# Acoustics_Connections_RP2040.net
KiCad netlist of a schematic drawn in Altium Designer
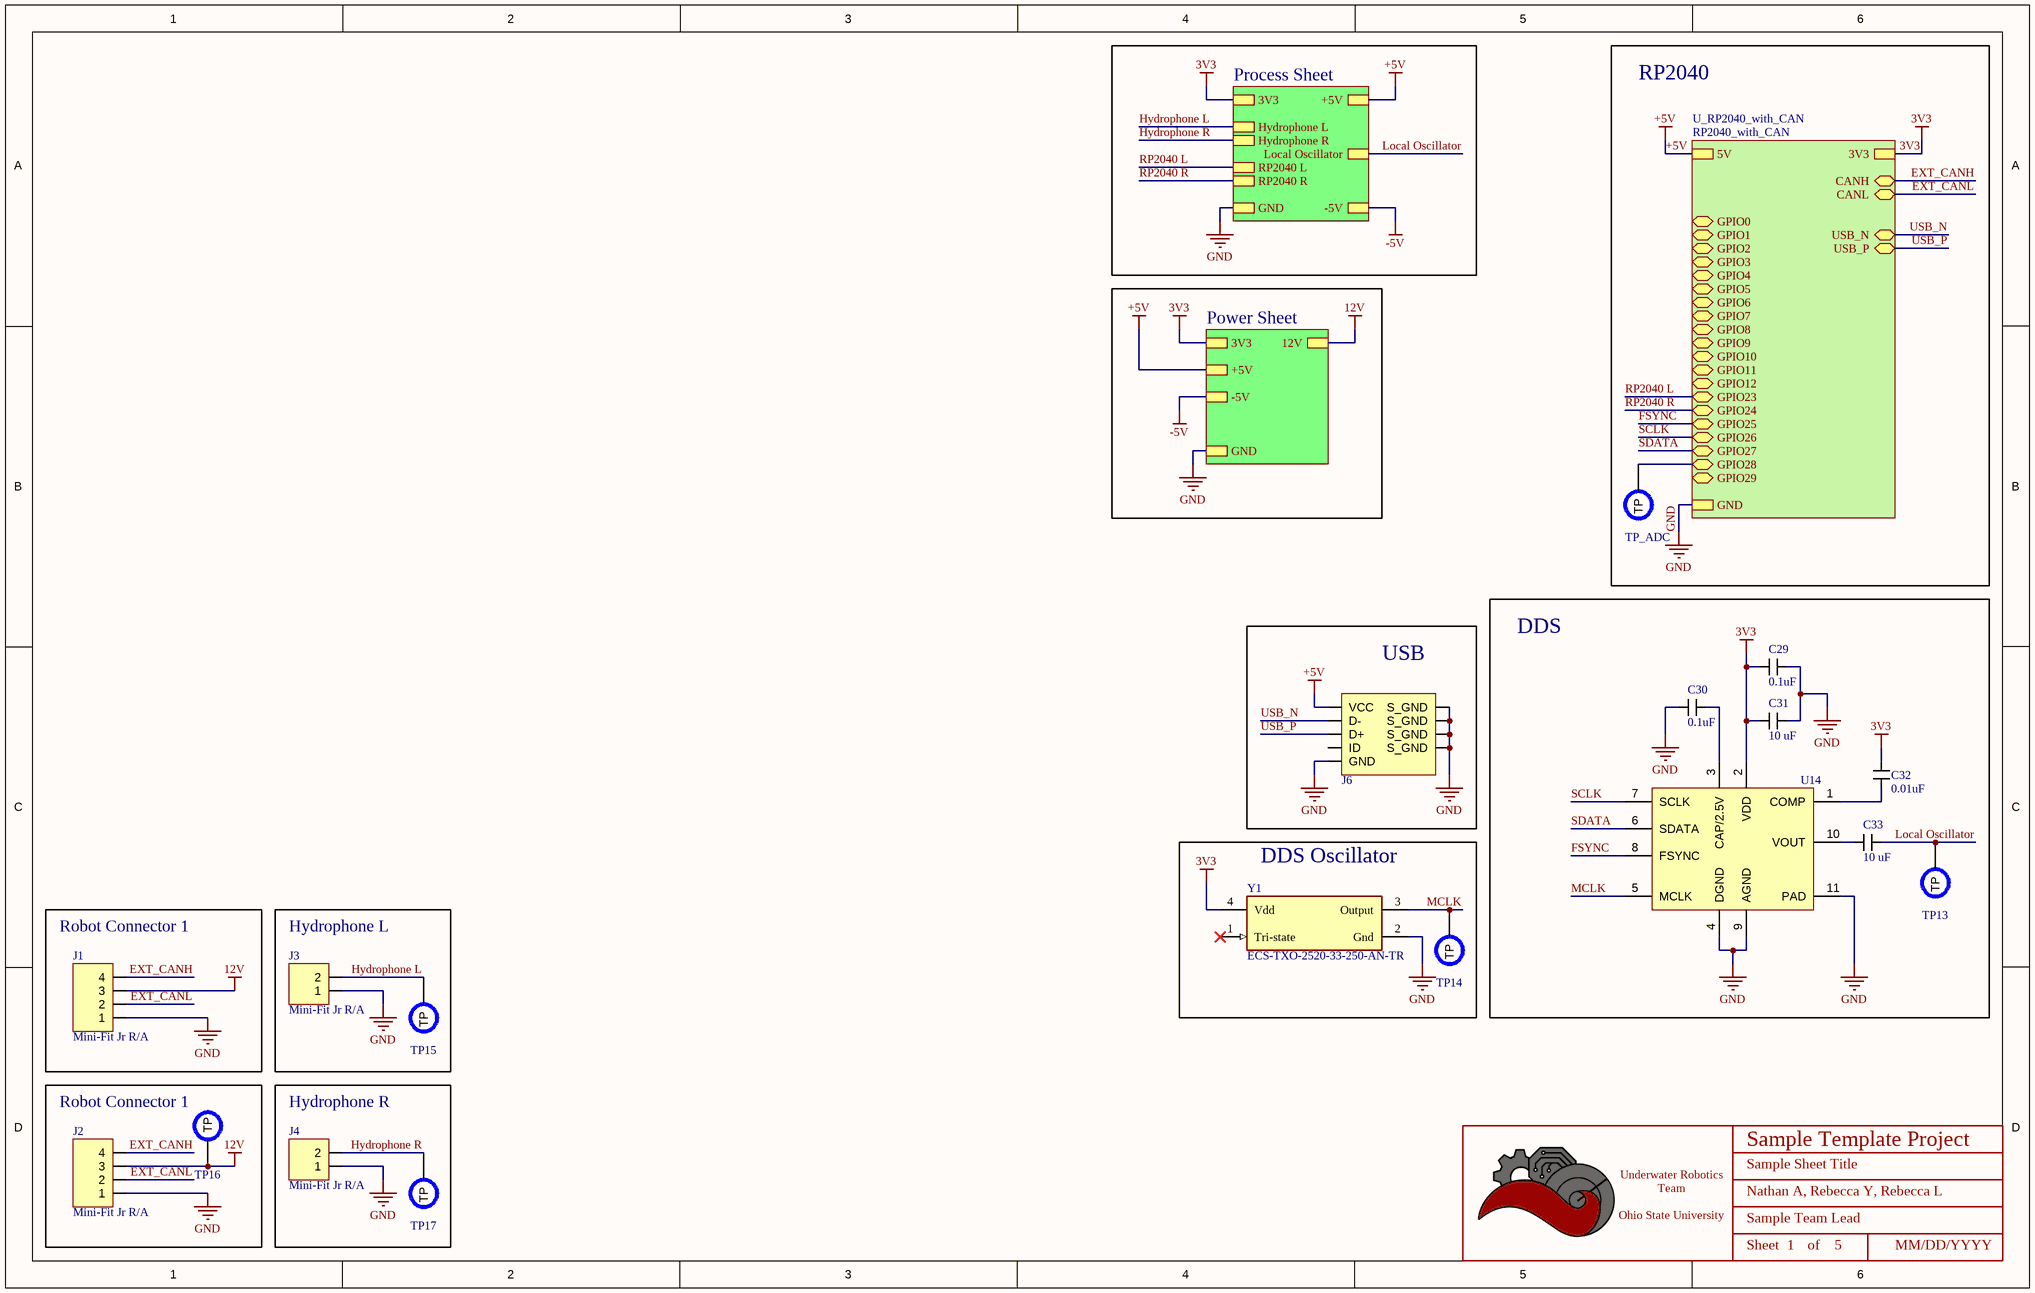
[diagram p0: [Acoustics] Connections & RP2040.SchDoc]

(export (version "E")
  (design (tool "Eeschema 10.0.6"))
  (components
    (comp (ref "C29")
      (value "0.1uF")
      (footprint "CAPACITOR_0603")
      (description "Cap 100nF 6.3V +/-10%\r\nCeramic 0603")
      (fields
        (field (name "TOLERANCE") "+/- 10%")
        (field (name "VOLTAGE") "6.3V")
        (field (name "MADE BY") "Flip B")
      )
      (libsource (lib "Capacitors") (part "CAPACITOR_0.1uF_0603"))
    )
    (comp (ref "C30")
      (value "0.1uF")
      (footprint "CAPACITOR_0603")
      (description "Cap 100nF 6.3V +/-10%\r\nCeramic 0603")
      (fields
        (field (name "TOLERANCE") "+/- 10%")
        (field (name "VOLTAGE") "6.3V")
        (field (name "MADE BY") "Flip B")
      )
      (libsource (lib "Capacitors") (part "CAPACITOR_0.1uF_0603"))
    )
    (comp (ref "C31")
      (value "10uF Ceramic 6.3V")
      (footprint "CAPACITOR_0603")
      (description "Cap 10uF 6.3V +/-20%\r\nCeramic 0603")
      (fields
        (field (name "TOLERANCE") "+/- 20%")
        (field (name "VOLTAGE") "6.3V")
        (field (name "VALUE (UF)") "10 uF")
        (field (name "MADE BY") "Flip B")
      )
      (libsource (lib "Capacitors") (part "CAPACITOR_10uF_0603"))
    )
    (comp (ref "C32")
      (value "0.01uF")
      (footprint "CAPACITOR_0603")
      (description "10000 pF ±10% 50V Ceramic Capacitor X7R 0603 (1608 Metric)")
      (fields
        (field (name "TOLERANCE") "+/- 10%")
        (field (name "VOLTAGE") "6.3V")
        (field (name "MADE BY") "Flip B")
      )
      (libsource (lib "Capacitors") (part "CAPACITOR_0.01uF_0603_50V"))
    )
    (comp (ref "C33")
      (value "10uF Ceramic 6.3V")
      (footprint "CAPACITOR_0603")
      (description "Cap 10uF 6.3V +/-20%\r\nCeramic 0603")
      (fields
        (field (name "TOLERANCE") "+/- 20%")
        (field (name "VOLTAGE") "6.3V")
        (field (name "VALUE (UF)") "10 uF")
        (field (name "MADE BY") "Flip B")
      )
      (libsource (lib "Capacitors") (part "CAPACITOR_10uF_0603"))
    )
    (comp (ref "J1")
      (value "Mini-Fit Jr R/A")
      (footprint "CONN_MOLEX_MINIFIT JR_4 POS_R/A")
      (description "Molex Minifit Jr. 5569 \r\n4 Pos R/A Natural")
      (fields (field (name "MANUFACTURER") "Molex") (field (name "CREATED BY") "Flip B"))
      (libsource (lib "Connectors") (part "CONN_MOLEX_MINIFIT JR_4POS_R/A"))
    )
    (comp (ref "J2")
      (value "Mini-Fit Jr R/A")
      (footprint "CONN_MOLEX_MINIFIT JR_4 POS_R/A")
      (description "Molex Minifit Jr. 5569 \r\n4 Pos R/A Natural")
      (fields (field (name "MANUFACTURER") "Molex") (field (name "CREATED BY") "Flip B"))
      (libsource (lib "Connectors") (part "CONN_MOLEX_MINIFIT JR_4POS_R/A"))
    )
    (comp (ref "J3")
      (value "Mini-Fit Jr R/A")
      (footprint "CONN_MOLEX_MINIFIT JR_2 POS_R/A")
      (description "Molex Minifit Jr. 5569 \r\n2 Pos R/A Natural")
      (fields (field (name "MANUFACTURER") "Molex") (field (name "CREATED BY") "Robert P"))
      (libsource (lib "Connectors") (part "CONN_MOLEX_MINIFIT JR_2POS_R/A"))
    )
    (comp (ref "J4")
      (value "Mini-Fit Jr R/A")
      (footprint "CONN_MOLEX_MINIFIT JR_2 POS_R/A")
      (description "Molex Minifit Jr. 5569 \r\n2 Pos R/A Natural")
      (fields (field (name "MANUFACTURER") "Molex") (field (name "CREATED BY") "Robert P"))
      (libsource (lib "Connectors") (part "CONN_MOLEX_MINIFIT JR_2POS_R/A"))
    )
    (comp (ref "J6")
      (value "USB_MICRO R/A")
      (footprint "CONN_MINIUSB")
      (description "Amphenol Micro USB-B\r\nUSB2.0 5 Pin Right Angle SMD")
      (fields (field (name "MANUFACTURER") "Amphenol") (field (name "CREATED BY") "Flip B"))
      (libsource (lib "Connectors") (part "CONN_MICROUSB"))
    )
    (comp (ref "TP13")
      (value "PCB Test Point")
      (footprint "TESTPOINT_1.2MM")
      (fields (field (name "MADE BY") "Robert Pafford"))
      (libsource (lib "Connectors") (part "TESTPOINT"))
    )
    (comp (ref "TP14")
      (value "PCB Test Point")
      (footprint "TESTPOINT_1.2MM")
      (fields (field (name "MADE BY") "Robert Pafford"))
      (libsource (lib "Connectors") (part "TESTPOINT"))
    )
    (comp (ref "TP15")
      (value "PCB Test Point")
      (footprint "TESTPOINT_1.2MM")
      (fields (field (name "MADE BY") "Robert Pafford"))
      (libsource (lib "Connectors") (part "TESTPOINT"))
    )
    (comp (ref "TP16")
      (value "PCB Test Point")
      (footprint "TESTPOINT_1.2MM")
      (fields (field (name "MADE BY") "Robert Pafford"))
      (libsource (lib "Connectors") (part "TESTPOINT"))
    )
    (comp (ref "TP17")
      (value "PCB Test Point")
      (footprint "TESTPOINT_1.2MM")
      (fields (field (name "MADE BY") "Robert Pafford"))
      (libsource (lib "Connectors") (part "TESTPOINT"))
    )
    (comp (ref "TP_ADC")
      (value "PCB Test Point")
      (footprint "TESTPOINT_1.2MM")
      (fields (field (name "MADE BY") "Robert Pafford"))
      (libsource (lib "Connectors") (part "TESTPOINT"))
    )
    (comp (ref "U14")
      (value "IC DDS 5MHZ 10BIT 10LFCSP")
      (footprint "CP-10-9")
      (description "Direct Digital Synthesis IC 10 b 5 MHz 28 b Tuning 10-LFCSP-WD (3x3)")
      (libsource (lib "Integrated Circuits") (part "AD9837ACPZ"))
    )
    (comp (ref "Y1")
      (value "ECS-TXO-2520-33-250-AN-TR")
      (footprint "FP-ECS-TXO-2520-MFG")
      (description "XTAL OSC TCXO 25.0000MHZ HCMOS")
      (libsource (lib "Altium Content Vault") (part "04cd953f3cf158082f8c09fbdb924ef"))
    )
  )
  (nets
    (net (code "1") (name "+5V") (class "Default")
      (node (ref "J6") (pin "1") (pinfunction "VCC_1") (pintype "passive"))
    )
    (net (code "3") (name "/EXT_CANH") (class "Default")
      (node (ref "J1") (pin "4") (pinfunction "4_4") (pintype "passive"))
      (node (ref "J2") (pin "4") (pinfunction "4_4") (pintype "passive"))
    )
    (net (code "4") (name "/EXT_CANL") (class "Default")
      (node (ref "J1") (pin "2") (pinfunction "2_2") (pintype "passive"))
      (node (ref "J2") (pin "2") (pinfunction "2_2") (pintype "passive"))
    )
    (net (code "5") (name "/FSYNC") (class "Default")
      (node (ref "U14") (pin "8") (pinfunction "FSYNC_8") (pintype "passive"))
    )
    (net (code "19") (name "/GPIO28") (class "Default")
      (node (ref "TP_ADC") (pin "TP") (pinfunction "TP_TP") (pintype "passive"))
    )
    (net (code "21") (name "/Hydrophone L") (class "Default")
      (node (ref "J3") (pin "2") (pinfunction "2_2") (pintype "passive"))
      (node (ref "TP15") (pin "TP") (pinfunction "TP_TP") (pintype "passive"))
    )
    (net (code "22") (name "/Hydrophone R") (class "Default")
      (node (ref "J4") (pin "2") (pinfunction "2_2") (pintype "passive"))
      (node (ref "TP17") (pin "TP") (pinfunction "TP_TP") (pintype "passive"))
    )
    (net (code "23") (name "/Local Oscillator") (class "Default")
      (node (ref "C33") (pin "2") (pinfunction "2_2") (pintype "passive"))
      (node (ref "TP13") (pin "TP") (pinfunction "TP_TP") (pintype "passive"))
    )
    (net (code "24") (name "/MCLK") (class "Default")
      (node (ref "TP14") (pin "TP") (pinfunction "TP_TP") (pintype "passive"))
      (node (ref "U14") (pin "5") (pinfunction "MCLK_5") (pintype "passive"))
      (node (ref "Y1") (pin "3") (pinfunction "Output_3") (pintype "tri_state"))
    )
    (net (code "27") (name "/SCLK") (class "Default")
      (node (ref "U14") (pin "7") (pinfunction "SCLK_7") (pintype "passive"))
    )
    (net (code "28") (name "/SDATA") (class "Default")
      (node (ref "U14") (pin "6") (pinfunction "SDATA_6") (pintype "passive"))
    )
    (net (code "29") (name "/USB_N") (class "Default")
      (node (ref "J6") (pin "2") (pinfunction "D-_2") (pintype "passive"))
    )
    (net (code "30") (name "/USB_P") (class "Default")
      (node (ref "J6") (pin "3") (pinfunction "D+_3") (pintype "passive"))
    )
    (net (code "31") (name "3V3") (class "Default")
      (node (ref "C29") (pin "2") (pinfunction "2_2") (pintype "passive"))
      (node (ref "C31") (pin "1") (pinfunction "1_1") (pintype "passive"))
      (node (ref "C32") (pin "1") (pinfunction "1_1") (pintype "passive"))
      (node (ref "U14") (pin "2") (pinfunction "VDD_2") (pintype "passive"))
      (node (ref "Y1") (pin "4") (pinfunction "Vdd_4") (pintype "power_in"))
    )
    (net (code "32") (name "12V") (class "Default")
      (node (ref "J1") (pin "3") (pinfunction "3_3") (pintype "passive"))
      (node (ref "J2") (pin "3") (pinfunction "3_3") (pintype "passive"))
      (node (ref "TP16") (pin "TP") (pinfunction "TP_TP") (pintype "passive"))
    )
    (net (code "33") (name "GND") (class "Default")
      (node (ref "C29") (pin "1") (pinfunction "1_1") (pintype "passive"))
      (node (ref "C30") (pin "1") (pinfunction "1_1") (pintype "passive"))
      (node (ref "C31") (pin "2") (pinfunction "2_2") (pintype "passive"))
      (node (ref "J1") (pin "1") (pinfunction "1_1") (pintype "passive"))
      (node (ref "J2") (pin "1") (pinfunction "1_1") (pintype "passive"))
      (node (ref "J3") (pin "1") (pinfunction "1_1") (pintype "passive"))
      (node (ref "J4") (pin "1") (pinfunction "1_1") (pintype "passive"))
      (node (ref "J6") (pin "5") (pinfunction "GND_5") (pintype "passive"))
      (node (ref "J6") (pin "6") (pinfunction "S_GND_6") (pintype "passive"))
      (node (ref "J6") (pin "7") (pinfunction "S_GND_7") (pintype "passive"))
      (node (ref "J6") (pin "8") (pinfunction "S_GND_8") (pintype "passive"))
      (node (ref "J6") (pin "9") (pinfunction "S_GND_9") (pintype "passive"))
      (node (ref "U14") (pin "11") (pinfunction "PAD_11") (pintype "passive"))
      (node (ref "U14") (pin "4") (pinfunction "DGND_4") (pintype "passive"))
      (node (ref "U14") (pin "9") (pinfunction "AGND_9") (pintype "passive"))
      (node (ref "Y1") (pin "2") (pinfunction "Gnd_2") (pintype "power_in"))
    )
    (net (code "34") (name "Net-(U14-CAP{slash}2.5V)") (class "Default")
      (node (ref "C30") (pin "2") (pinfunction "2_2") (pintype "passive"))
      (node (ref "U14") (pin "3") (pinfunction "CAP/2.5V_3") (pintype "passive"))
    )
    (net (code "35") (name "Net-(U14-COMP)") (class "Default")
      (node (ref "C32") (pin "2") (pinfunction "2_2") (pintype "passive"))
      (node (ref "U14") (pin "1") (pinfunction "COMP_1") (pintype "passive"))
    )
    (net (code "36") (name "Net-(U14-VOUT)") (class "Default")
      (node (ref "C33") (pin "1") (pinfunction "1_1") (pintype "passive"))
      (node (ref "U14") (pin "10") (pinfunction "VOUT_10") (pintype "passive"))
    )
    (net (code "37") (name "unconnected-(J6-ID-Pad4)") (class "Default")
      (node (ref "J6") (pin "4") (pinfunction "ID_4") (pintype "passive"))
    )
    (net (code "38") (name "unconnected-(Y1-Tri-state-Pad1)") (class "Default")
      (node (ref "Y1") (pin "1") (pinfunction "Tri-state_1") (pintype "input+no_connect"))
    )
  )
)
